# Mainboard.net
KiCad netlist of a schematic drawn in EAGLE
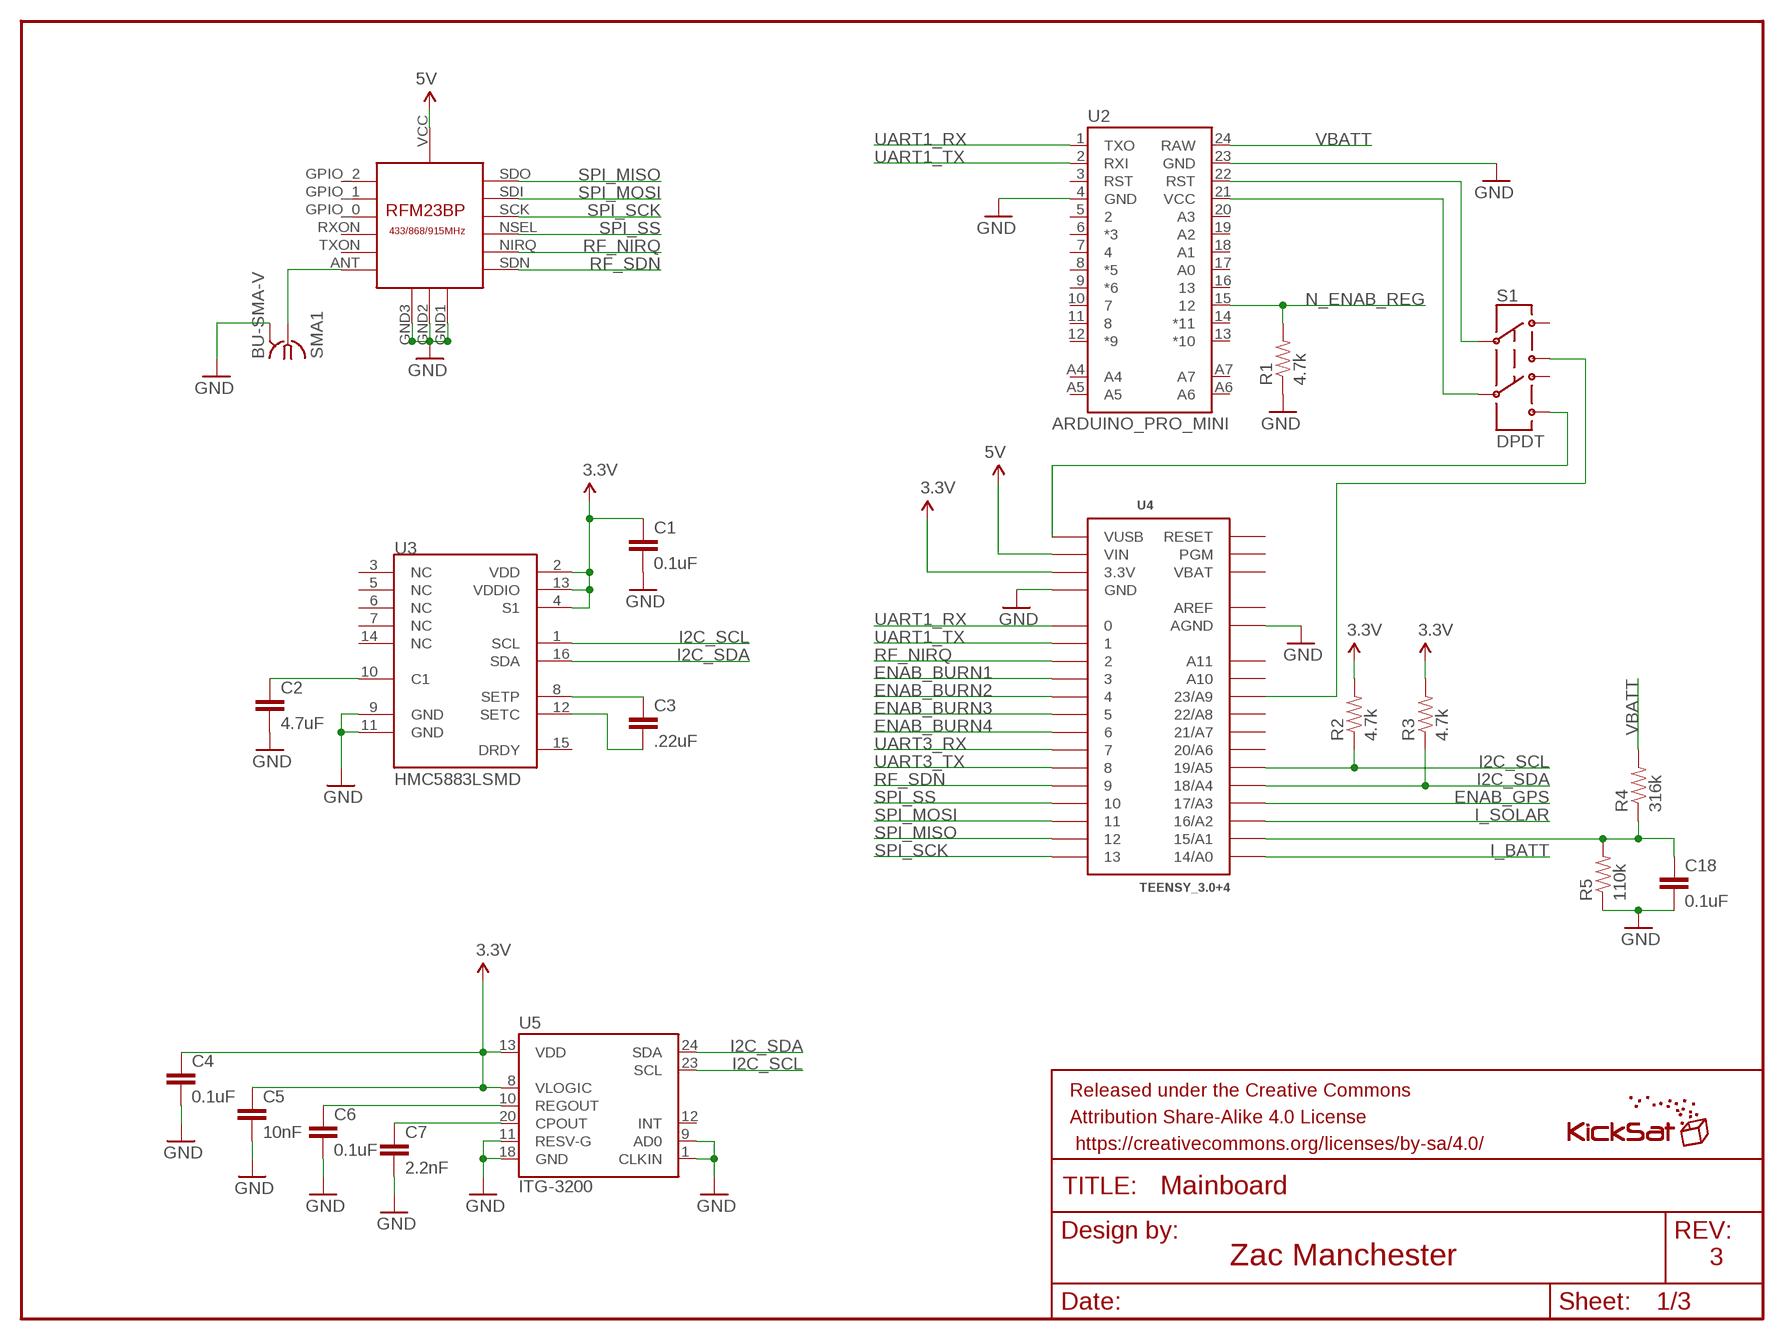
[diagram p0: schematic, sheet 1]
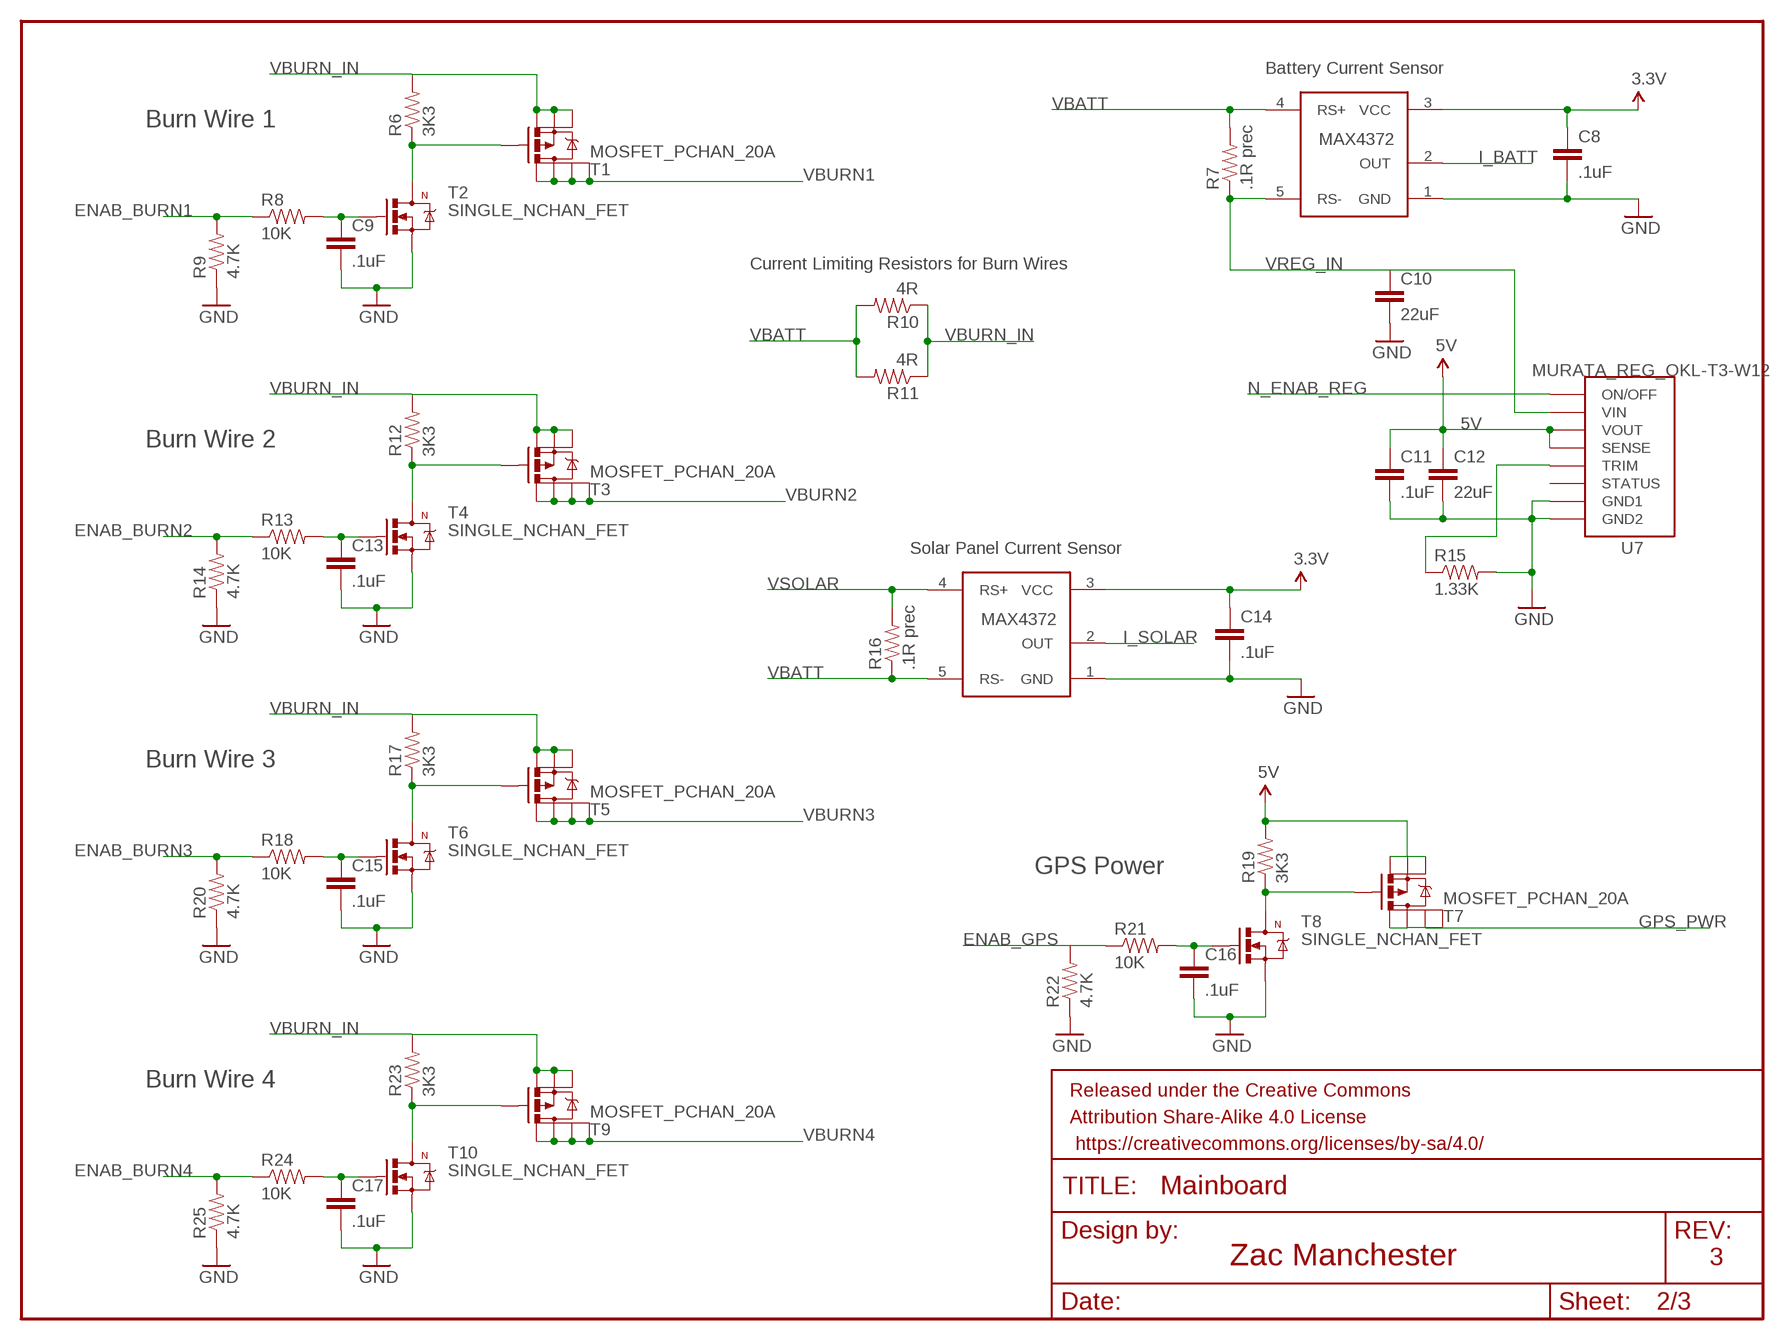
[diagram p1: schematic, sheet 2]
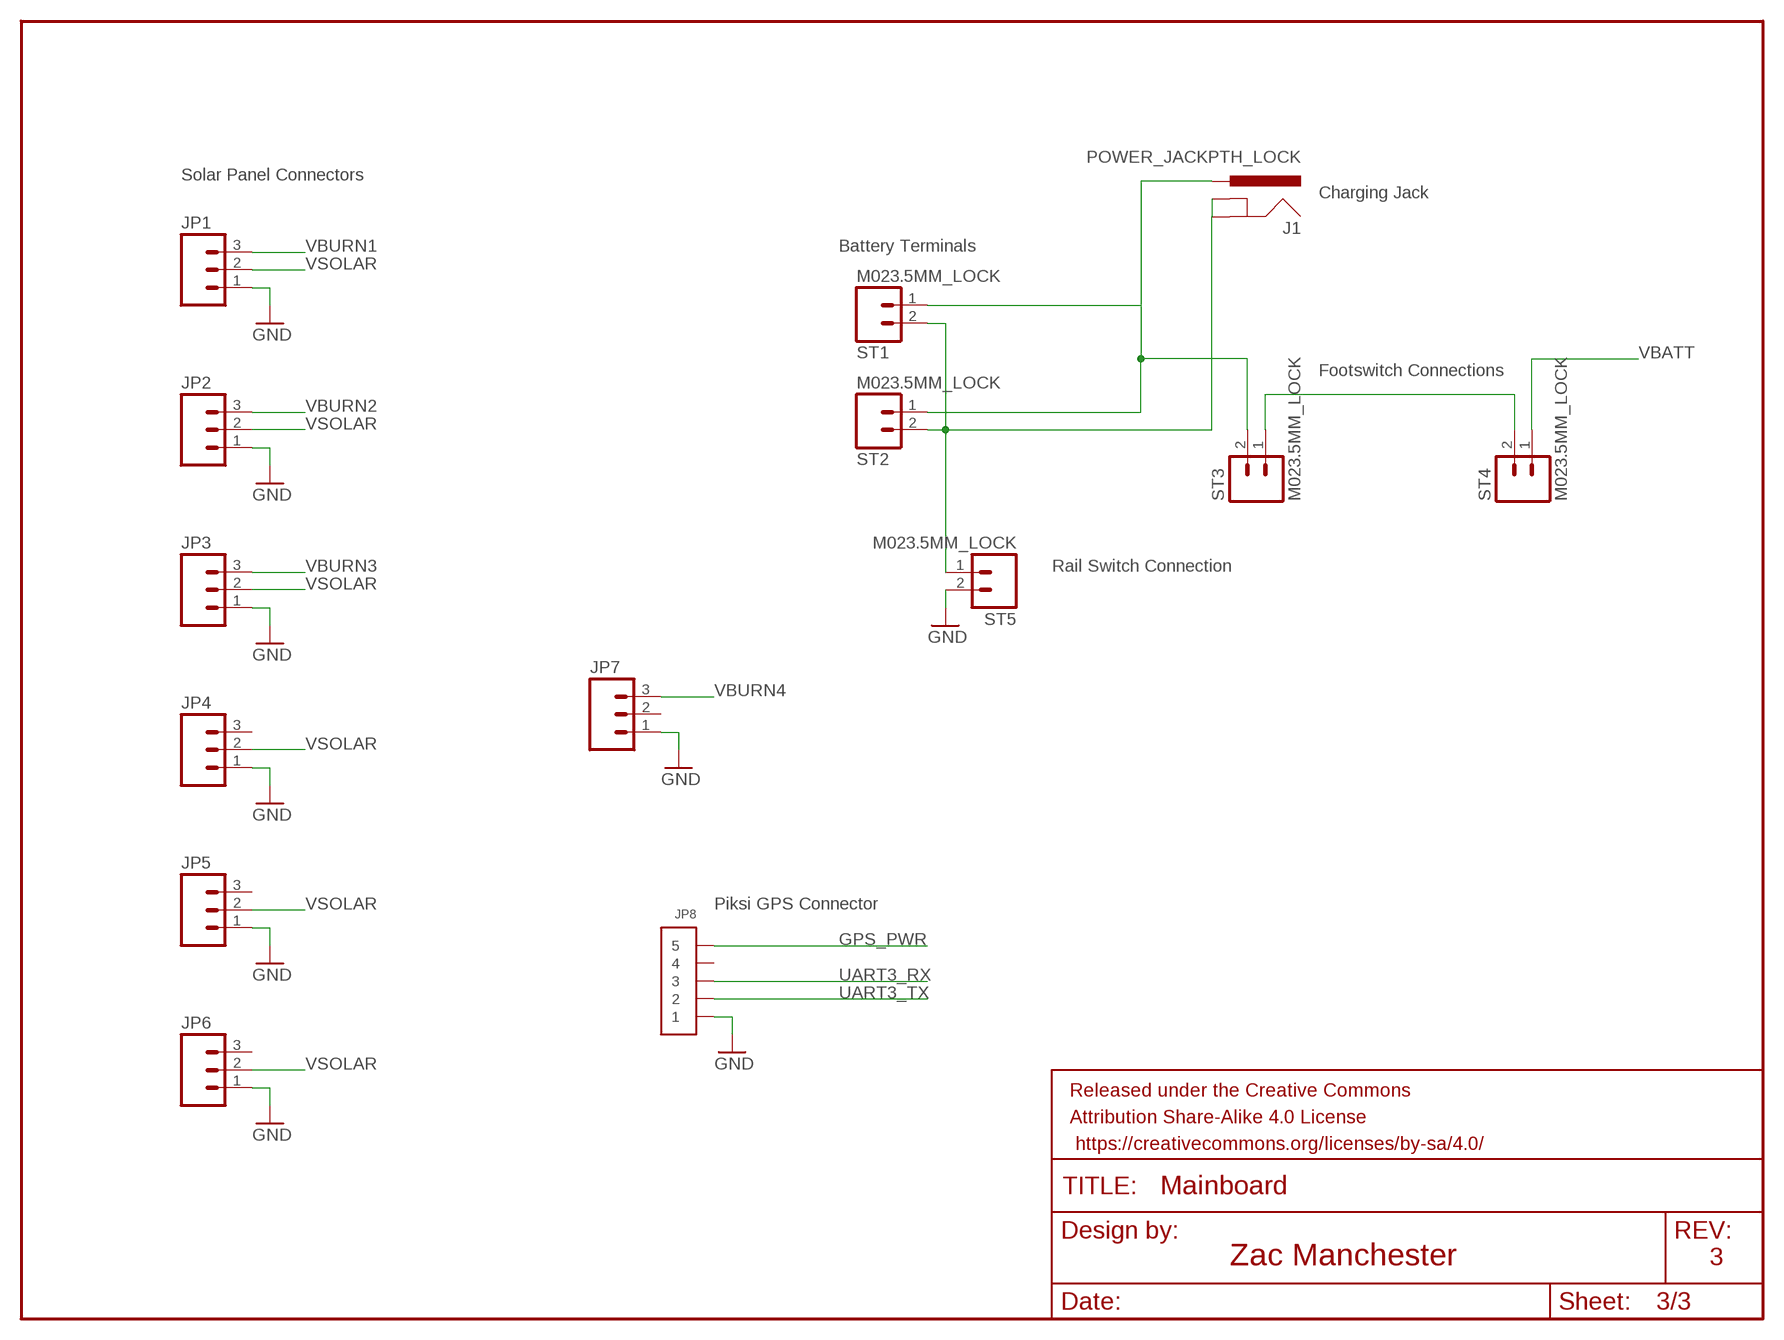
[diagram p2: schematic, sheet 3]

(export (version "E")
  (design (tool "Eeschema 10.0.6"))
  (components
    (comp (ref "C8")
      (value ".1uF")
      (footprint "eagle-import:0805")
      (libsource (lib "eagle-import") (part "CAP0805"))
    )
    (comp (ref "C9")
      (value ".1uF")
      (footprint "eagle-import:0805")
      (libsource (lib "eagle-import") (part "CAP0805"))
    )
    (comp (ref "C10")
      (value "22uF")
      (footprint "eagle-import:1206")
      (libsource (lib "eagle-import") (part "CAP1206"))
    )
    (comp (ref "C11")
      (value ".1uF")
      (footprint "eagle-import:0805")
      (libsource (lib "eagle-import") (part "CAP0805"))
    )
    (comp (ref "C12")
      (value "22uF")
      (footprint "eagle-import:1206")
      (libsource (lib "eagle-import") (part "CAP1206"))
    )
    (comp (ref "C13")
      (value ".1uF")
      (footprint "eagle-import:0805")
      (libsource (lib "eagle-import") (part "CAP0805"))
    )
    (comp (ref "C14")
      (value ".1uF")
      (footprint "eagle-import:0805")
      (libsource (lib "eagle-import") (part "CAP0805"))
    )
    (comp (ref "C15")
      (value ".1uF")
      (footprint "eagle-import:0805")
      (libsource (lib "eagle-import") (part "CAP0805"))
    )
    (comp (ref "C16")
      (value ".1uF")
      (footprint "eagle-import:0805")
      (libsource (lib "eagle-import") (part "CAP0805"))
    )
    (comp (ref "C17")
      (value ".1uF")
      (footprint "eagle-import:0805")
      (libsource (lib "eagle-import") (part "CAP0805"))
    )
    (comp (ref "FRAME2")
      (value "FRAME-LETTER")
      (footprint "eagle-import:CREATIVE_COMMONS")
      (libsource (lib "eagle-import") (part "FRAME-LETTER"))
    )
    (comp (ref "R6")
      (value "3K3")
      (footprint "eagle-import:0805")
      (libsource (lib "eagle-import") (part "RESISTOR0805-RES"))
    )
    (comp (ref "R7")
      (value ".1R prec")
      (footprint "eagle-import:0805")
      (libsource (lib "eagle-import") (part "RESISTOR0805-RES"))
    )
    (comp (ref "R8")
      (value "10K")
      (footprint "eagle-import:0805")
      (libsource (lib "eagle-import") (part "RESISTOR0805-RES"))
    )
    (comp (ref "R9")
      (value "4.7K")
      (footprint "eagle-import:0805")
      (libsource (lib "eagle-import") (part "RESISTOR0805-RES"))
    )
    (comp (ref "R10")
      (value "4R")
      (footprint "eagle-import:R2512")
      (libsource (lib "eagle-import") (part "RESISTOR2512"))
    )
    (comp (ref "R11")
      (value "4R")
      (footprint "eagle-import:R2512")
      (libsource (lib "eagle-import") (part "RESISTOR2512"))
    )
    (comp (ref "R12")
      (value "3K3")
      (footprint "eagle-import:0805")
      (libsource (lib "eagle-import") (part "RESISTOR0805-RES"))
    )
    (comp (ref "R13")
      (value "10K")
      (footprint "eagle-import:0805")
      (libsource (lib "eagle-import") (part "RESISTOR0805-RES"))
    )
    (comp (ref "R14")
      (value "4.7K")
      (footprint "eagle-import:0805")
      (libsource (lib "eagle-import") (part "RESISTOR0805-RES"))
    )
    (comp (ref "R15")
      (value "1.33K")
      (footprint "eagle-import:0805")
      (libsource (lib "eagle-import") (part "RESISTOR0805-RES"))
    )
    (comp (ref "R16")
      (value ".1R prec")
      (footprint "eagle-import:0805")
      (libsource (lib "eagle-import") (part "RESISTOR0805-RES"))
    )
    (comp (ref "R17")
      (value "3K3")
      (footprint "eagle-import:0805")
      (libsource (lib "eagle-import") (part "RESISTOR0805-RES"))
    )
    (comp (ref "R18")
      (value "10K")
      (footprint "eagle-import:0805")
      (libsource (lib "eagle-import") (part "RESISTOR0805-RES"))
    )
    (comp (ref "R19")
      (value "3K3")
      (footprint "eagle-import:0805")
      (libsource (lib "eagle-import") (part "RESISTOR0805-RES"))
    )
    (comp (ref "R20")
      (value "4.7K")
      (footprint "eagle-import:0805")
      (libsource (lib "eagle-import") (part "RESISTOR0805-RES"))
    )
    (comp (ref "R21")
      (value "10K")
      (footprint "eagle-import:0805")
      (libsource (lib "eagle-import") (part "RESISTOR0805-RES"))
    )
    (comp (ref "R22")
      (value "4.7K")
      (footprint "eagle-import:0805")
      (libsource (lib "eagle-import") (part "RESISTOR0805-RES"))
    )
    (comp (ref "R23")
      (value "3K3")
      (footprint "eagle-import:0805")
      (libsource (lib "eagle-import") (part "RESISTOR0805-RES"))
    )
    (comp (ref "R24")
      (value "10K")
      (footprint "eagle-import:0805")
      (libsource (lib "eagle-import") (part "RESISTOR0805-RES"))
    )
    (comp (ref "R25")
      (value "4.7K")
      (footprint "eagle-import:0805")
      (libsource (lib "eagle-import") (part "RESISTOR0805-RES"))
    )
    (comp (ref "T1")
      (value "MOSFET_PCHAN_20A")
      (footprint "eagle-import:SO8")
      (libsource (lib "eagle-import") (part "MOSFET_PCHAN_20A"))
    )
    (comp (ref "T2")
      (value "SINGLE_NCHAN_FET")
      (footprint "eagle-import:SOT23-3")
      (libsource (lib "eagle-import") (part "SINGLE_NCHAN_FET"))
    )
    (comp (ref "T3")
      (value "MOSFET_PCHAN_20A")
      (footprint "eagle-import:SO8")
      (libsource (lib "eagle-import") (part "MOSFET_PCHAN_20A"))
    )
    (comp (ref "T4")
      (value "SINGLE_NCHAN_FET")
      (footprint "eagle-import:SOT23-3")
      (libsource (lib "eagle-import") (part "SINGLE_NCHAN_FET"))
    )
    (comp (ref "T5")
      (value "MOSFET_PCHAN_20A")
      (footprint "eagle-import:SO8")
      (libsource (lib "eagle-import") (part "MOSFET_PCHAN_20A"))
    )
    (comp (ref "T6")
      (value "SINGLE_NCHAN_FET")
      (footprint "eagle-import:SOT23-3")
      (libsource (lib "eagle-import") (part "SINGLE_NCHAN_FET"))
    )
    (comp (ref "T7")
      (value "MOSFET_PCHAN_20A")
      (footprint "eagle-import:SO8")
      (libsource (lib "eagle-import") (part "MOSFET_PCHAN_20A"))
    )
    (comp (ref "T8")
      (value "SINGLE_NCHAN_FET")
      (footprint "eagle-import:SOT23-3")
      (libsource (lib "eagle-import") (part "SINGLE_NCHAN_FET"))
    )
    (comp (ref "T9")
      (value "MOSFET_PCHAN_20A")
      (footprint "eagle-import:SO8")
      (libsource (lib "eagle-import") (part "MOSFET_PCHAN_20A"))
    )
    (comp (ref "T10")
      (value "SINGLE_NCHAN_FET")
      (footprint "eagle-import:SOT23-3")
      (libsource (lib "eagle-import") (part "SINGLE_NCHAN_FET"))
    )
    (comp (ref "U6")
      (value "CURRENT_MAX4372")
      (footprint "eagle-import:SOT23-5")
      (libsource (lib "eagle-import") (part "CURRENT_MAX4372"))
    )
    (comp (ref "U7")
      (value "MURATA_REG_OKL-T3-W12")
      (footprint "eagle-import:MURATA_REG_OKL-T6-W12")
      (libsource (lib "eagle-import") (part "MURATA_REG_OKL-T6-W12"))
    )
    (comp (ref "U8")
      (value "CURRENT_MAX4372")
      (footprint "eagle-import:SOT23-5")
      (libsource (lib "eagle-import") (part "CURRENT_MAX4372"))
    )
    (comp (ref "FRAME3")
      (value "FRAME-LETTER")
      (footprint "eagle-import:CREATIVE_COMMONS")
      (libsource (lib "eagle-import") (part "FRAME-LETTER"))
    )
    (comp (ref "J1")
      (value "POWER_JACKPTH_LOCK")
      (footprint "eagle-import:POWER_JACK_PTH_LOCK")
      (libsource (lib "eagle-import") (part "POWER_JACKPTH_LOCK"))
    )
    (comp (ref "JP1")
      (value "M03POLAR_LOCK")
      (footprint "eagle-import:MOLEX-1X3_LOCK")
      (libsource (lib "eagle-import") (part "M03POLAR_LOCK"))
    )
    (comp (ref "JP2")
      (value "M03POLAR_LOCK")
      (footprint "eagle-import:MOLEX-1X3_LOCK")
      (libsource (lib "eagle-import") (part "M03POLAR_LOCK"))
    )
    (comp (ref "JP3")
      (value "M03POLAR_LOCK")
      (footprint "eagle-import:MOLEX-1X3_LOCK")
      (libsource (lib "eagle-import") (part "M03POLAR_LOCK"))
    )
    (comp (ref "JP4")
      (value "M03POLAR_LOCK")
      (footprint "eagle-import:MOLEX-1X3_LOCK")
      (libsource (lib "eagle-import") (part "M03POLAR_LOCK"))
    )
    (comp (ref "JP5")
      (value "M03POLAR_LOCK")
      (footprint "eagle-import:MOLEX-1X3_LOCK")
      (libsource (lib "eagle-import") (part "M03POLAR_LOCK"))
    )
    (comp (ref "JP6")
      (value "M03POLAR_LOCK")
      (footprint "eagle-import:MOLEX-1X3_LOCK")
      (libsource (lib "eagle-import") (part "M03POLAR_LOCK"))
    )
    (comp (ref "JP7")
      (value "M03POLAR_LOCK")
      (footprint "eagle-import:MOLEX-1X3_LOCK")
      (libsource (lib "eagle-import") (part "M03POLAR_LOCK"))
    )
    (comp (ref "JP8")
      (value "CONN_5-1-53261")
      (footprint "eagle-import:PB-53261-05")
      (libsource (lib "eagle-import") (part "CONN_5-1-53261"))
    )
    (comp (ref "ST1")
      (value "M023.5MM_LOCK")
      (footprint "eagle-import:SCREWTERMINAL-3.5MM-2_LOCK")
      (libsource (lib "eagle-import") (part "M023.5MM_LOCK"))
    )
    (comp (ref "ST2")
      (value "M023.5MM_LOCK")
      (footprint "eagle-import:SCREWTERMINAL-3.5MM-2_LOCK")
      (libsource (lib "eagle-import") (part "M023.5MM_LOCK"))
    )
    (comp (ref "ST3")
      (value "M023.5MM_LOCK")
      (footprint "eagle-import:SCREWTERMINAL-3.5MM-2_LOCK")
      (libsource (lib "eagle-import") (part "M023.5MM_LOCK"))
    )
    (comp (ref "ST4")
      (value "M023.5MM_LOCK")
      (footprint "eagle-import:SCREWTERMINAL-3.5MM-2_LOCK")
      (libsource (lib "eagle-import") (part "M023.5MM_LOCK"))
    )
    (comp (ref "ST5")
      (value "M023.5MM_LOCK")
      (footprint "eagle-import:SCREWTERMINAL-3.5MM-2_LOCK")
      (libsource (lib "eagle-import") (part "M023.5MM_LOCK"))
    )
    (comp (ref "C1")
      (value "0.1uF")
      (footprint "eagle-import:0805")
      (libsource (lib "eagle-import") (part "CAP0805"))
    )
    (comp (ref "C2")
      (value "4.7uF")
      (footprint "eagle-import:0805")
      (libsource (lib "eagle-import") (part "CAP0805"))
    )
    (comp (ref "C3")
      (value ".22uF")
      (footprint "eagle-import:0805")
      (libsource (lib "eagle-import") (part "CAP0805"))
    )
    (comp (ref "C4")
      (value "0.1uF")
      (footprint "eagle-import:0805")
      (libsource (lib "eagle-import") (part "CAP0805"))
    )
    (comp (ref "C5")
      (value "10nF")
      (footprint "eagle-import:0805")
      (libsource (lib "eagle-import") (part "CAP0805"))
    )
    (comp (ref "C6")
      (value "0.1uF")
      (footprint "eagle-import:0805")
      (libsource (lib "eagle-import") (part "CAP0805"))
    )
    (comp (ref "C7")
      (value "2.2nF")
      (footprint "eagle-import:0805")
      (libsource (lib "eagle-import") (part "CAP0805"))
    )
    (comp (ref "C18")
      (value "0.1uF")
      (footprint "eagle-import:0805")
      (libsource (lib "eagle-import") (part "CAP0805"))
    )
    (comp (ref "FRAME1")
      (value "FRAME-LETTER")
      (footprint "eagle-import:CREATIVE_COMMONS")
      (libsource (lib "eagle-import") (part "FRAME-LETTER"))
    )
    (comp (ref "R1")
      (value "4.7k")
      (footprint "eagle-import:0805")
      (libsource (lib "eagle-import") (part "RESISTOR0805-RES"))
    )
    (comp (ref "R2")
      (value "4.7k")
      (footprint "eagle-import:0805")
      (libsource (lib "eagle-import") (part "RESISTOR0805-RES"))
    )
    (comp (ref "R3")
      (value "4.7k")
      (footprint "eagle-import:0805")
      (libsource (lib "eagle-import") (part "RESISTOR0805-RES"))
    )
    (comp (ref "R4")
      (value "316k")
      (footprint "eagle-import:0805")
      (libsource (lib "eagle-import") (part "RESISTOR0805-RES"))
    )
    (comp (ref "R5")
      (value "110k")
      (footprint "eagle-import:0805")
      (libsource (lib "eagle-import") (part "RESISTOR0805-RES"))
    )
    (comp (ref "S1")
      (value "DPDT")
      (footprint "eagle-import:AYZ0202")
      (libsource (lib "eagle-import") (part "SWITCH-DPDTAYZ0202"))
    )
    (comp (ref "SMA1")
      (value "BU-SMA-V")
      (footprint "eagle-import:BU-SMA-V")
      (libsource (lib "eagle-import") (part "BU-SMA-V"))
    )
    (comp (ref "U$3")
      (value "KICKSAT_LOGO")
      (footprint "eagle-import:KICKSAT_LOGO")
      (libsource (lib "eagle-import") (part "KICKSAT_LOGO"))
    )
    (comp (ref "U1")
      (value "RFM23BP")
      (footprint "eagle-import:RFM23BP")
      (libsource (lib "eagle-import") (part "RFM23BP"))
    )
    (comp (ref "U2")
      (value "ARDUINO_PRO_MINI")
      (footprint "eagle-import:ARDUINO_PRO_MINI")
      (libsource (lib "eagle-import") (part "ARDUINO_PRO_MINI"))
    )
    (comp (ref "U3")
      (value "HMC5883LSMD")
      (footprint "eagle-import:16LPCC")
      (libsource (lib "eagle-import") (part "HMC5883LSMD"))
    )
    (comp (ref "U4")
      (value "TEENSY_3.0+4")
      (footprint "eagle-import:TEENSY_3.0+4")
      (libsource (lib "eagle-import") (part "TEENSY_3.0+4"))
    )
    (comp (ref "U5")
      (value "ITG-3200")
      (footprint "eagle-import:QFN-24")
      (libsource (lib "eagle-import") (part "ITG-3200"))
    )
  )
  (nets
    (net (code "1") (name "3.3V") (class "Default")
      (node (ref "C1") (pin "1") (pinfunction "1_1") (pintype "passive"))
      (node (ref "C14") (pin "1") (pinfunction "1_1") (pintype "passive"))
      (node (ref "C4") (pin "1") (pinfunction "1_1") (pintype "passive"))
      (node (ref "C5") (pin "1") (pinfunction "1_1") (pintype "passive"))
      (node (ref "C8") (pin "1") (pinfunction "1_1") (pintype "passive"))
      (node (ref "R2") (pin "2") (pinfunction "2_2") (pintype "passive"))
      (node (ref "R3") (pin "2") (pinfunction "2_2") (pintype "passive"))
      (node (ref "U3") (pin "13") (pinfunction "VDDIO_13") (pintype "bidirectional"))
      (node (ref "U3") (pin "2") (pinfunction "VDD_2") (pintype "bidirectional"))
      (node (ref "U3") (pin "4") (pinfunction "S1_4") (pintype "bidirectional"))
      (node (ref "U4") (pin "3.3V") (pinfunction "3.3V_3.3V") (pintype "power_in"))
      (node (ref "U4") (pin "3.3V1") (pinfunction "3.3V_3.3V1") (pintype "power_in"))
      (node (ref "U5") (pin "13") (pinfunction "VDD_13") (pintype "bidirectional"))
      (node (ref "U5") (pin "8") (pinfunction "VLOGIC_8") (pintype "bidirectional"))
      (node (ref "U6") (pin "3") (pinfunction "VCC_3") (pintype "bidirectional"))
      (node (ref "U8") (pin "3") (pinfunction "VCC_3") (pintype "bidirectional"))
    )
    (net (code "2") (name "5V") (class "Default")
      (node (ref "C11") (pin "1") (pinfunction "1_1") (pintype "passive"))
      (node (ref "C12") (pin "1") (pinfunction "1_1") (pintype "passive"))
      (node (ref "R19") (pin "2") (pinfunction "2_2") (pintype "passive"))
      (node (ref "T7") (pin "1") (pinfunction "S_1") (pintype "passive"))
      (node (ref "T7") (pin "2") (pinfunction "S_2") (pintype "passive"))
      (node (ref "T7") (pin "3") (pinfunction "S_3") (pintype "passive"))
      (node (ref "U1") (pin "VCC") (pinfunction "VCC_VCC") (pintype "power_in"))
      (node (ref "U4") (pin "VIN") (pinfunction "VIN_VIN") (pintype "power_in"))
      (node (ref "U7") (pin "4") (pinfunction "VOUT_4") (pintype "bidirectional"))
      (node (ref "U7") (pin "5") (pinfunction "SENSE_5") (pintype "bidirectional"))
    )
    (net (code "3") (name "AREF") (class "Default")
      (node (ref "U4") (pin "AREF") (pinfunction "AREF_AREF") (pintype "power_in"))
    )
    (net (code "4") (name "ENAB_BURN1") (class "Default")
      (node (ref "R8") (pin "1") (pinfunction "1_1") (pintype "passive"))
      (node (ref "R9") (pin "2") (pinfunction "2_2") (pintype "passive"))
      (node (ref "U4") (pin "3") (pinfunction "3_3") (pintype "bidirectional"))
    )
    (net (code "5") (name "ENAB_BURN2") (class "Default")
      (node (ref "R13") (pin "1") (pinfunction "1_1") (pintype "passive"))
      (node (ref "R14") (pin "2") (pinfunction "2_2") (pintype "passive"))
      (node (ref "U4") (pin "4") (pinfunction "4_4") (pintype "bidirectional"))
    )
    (net (code "6") (name "ENAB_BURN3") (class "Default")
      (node (ref "R18") (pin "1") (pinfunction "1_1") (pintype "passive"))
      (node (ref "R20") (pin "2") (pinfunction "2_2") (pintype "passive"))
      (node (ref "U4") (pin "5") (pinfunction "5_5") (pintype "bidirectional"))
    )
    (net (code "7") (name "ENAB_BURN4") (class "Default")
      (node (ref "R24") (pin "1") (pinfunction "1_1") (pintype "passive"))
      (node (ref "R25") (pin "2") (pinfunction "2_2") (pintype "passive"))
      (node (ref "U4") (pin "6") (pinfunction "6_6") (pintype "bidirectional"))
    )
    (net (code "8") (name "ENAB_GPS") (class "Default")
      (node (ref "R21") (pin "1") (pinfunction "1_1") (pintype "passive"))
      (node (ref "R22") (pin "2") (pinfunction "2_2") (pintype "passive"))
      (node (ref "U4") (pin "17/A3") (pinfunction "17/A3_17/A3") (pintype "bidirectional"))
    )
    (net (code "9") (name "GND") (class "Default")
      (node (ref "C1") (pin "2") (pinfunction "2_2") (pintype "passive"))
      (node (ref "C10") (pin "2") (pinfunction "2_2") (pintype "passive"))
      (node (ref "C11") (pin "2") (pinfunction "2_2") (pintype "passive"))
      (node (ref "C12") (pin "2") (pinfunction "2_2") (pintype "passive"))
      (node (ref "C13") (pin "2") (pinfunction "2_2") (pintype "passive"))
      (node (ref "C14") (pin "2") (pinfunction "2_2") (pintype "passive"))
      (node (ref "C15") (pin "2") (pinfunction "2_2") (pintype "passive"))
      (node (ref "C16") (pin "2") (pinfunction "2_2") (pintype "passive"))
      (node (ref "C17") (pin "2") (pinfunction "2_2") (pintype "passive"))
      (node (ref "C18") (pin "2") (pinfunction "2_2") (pintype "passive"))
      (node (ref "C2") (pin "2") (pinfunction "2_2") (pintype "passive"))
      (node (ref "C4") (pin "2") (pinfunction "2_2") (pintype "passive"))
      (node (ref "C5") (pin "2") (pinfunction "2_2") (pintype "passive"))
      (node (ref "C6") (pin "2") (pinfunction "2_2") (pintype "passive"))
      (node (ref "C7") (pin "2") (pinfunction "2_2") (pintype "passive"))
      (node (ref "C8") (pin "2") (pinfunction "2_2") (pintype "passive"))
      (node (ref "C9") (pin "2") (pinfunction "2_2") (pintype "passive"))
      (node (ref "JP1") (pin "1") (pinfunction "1_1") (pintype "passive"))
      (node (ref "JP2") (pin "1") (pinfunction "1_1") (pintype "passive"))
      (node (ref "JP3") (pin "1") (pinfunction "1_1") (pintype "passive"))
      (node (ref "JP4") (pin "1") (pinfunction "1_1") (pintype "passive"))
      (node (ref "JP5") (pin "1") (pinfunction "1_1") (pintype "passive"))
      (node (ref "JP6") (pin "1") (pinfunction "1_1") (pintype "passive"))
      (node (ref "JP7") (pin "1") (pinfunction "1_1") (pintype "passive"))
      (node (ref "JP8") (pin "1") (pinfunction "1_1") (pintype "bidirectional"))
      (node (ref "R1") (pin "1") (pinfunction "1_1") (pintype "passive"))
      (node (ref "R14") (pin "1") (pinfunction "1_1") (pintype "passive"))
      (node (ref "R15") (pin "2") (pinfunction "2_2") (pintype "passive"))
      (node (ref "R20") (pin "1") (pinfunction "1_1") (pintype "passive"))
      (node (ref "R22") (pin "1") (pinfunction "1_1") (pintype "passive"))
      (node (ref "R25") (pin "1") (pinfunction "1_1") (pintype "passive"))
      (node (ref "R5") (pin "1") (pinfunction "1_1") (pintype "passive"))
      (node (ref "R9") (pin "1") (pinfunction "1_1") (pintype "passive"))
      (node (ref "SMA1") (pin "2") (pinfunction "2_2") (pintype "passive"))
      (node (ref "SMA1") (pin "3") (pinfunction "2_3") (pintype "passive"))
      (node (ref "SMA1") (pin "4") (pinfunction "2_4") (pintype "passive"))
      (node (ref "SMA1") (pin "5") (pinfunction "2_5") (pintype "passive"))
      (node (ref "ST5") (pin "2") (pinfunction "2_2") (pintype "passive"))
      (node (ref "T10") (pin "2") (pinfunction "S_2") (pintype "passive"))
      (node (ref "T2") (pin "2") (pinfunction "S_2") (pintype "passive"))
      (node (ref "T4") (pin "2") (pinfunction "S_2") (pintype "passive"))
      (node (ref "T6") (pin "2") (pinfunction "S_2") (pintype "passive"))
      (node (ref "T8") (pin "2") (pinfunction "S_2") (pintype "passive"))
      (node (ref "U1") (pin "GND1") (pinfunction "GND1_GND1") (pintype "power_in"))
      (node (ref "U1") (pin "GND2") (pinfunction "GND2_GND2") (pintype "power_in"))
      (node (ref "U1") (pin "GND3") (pinfunction "GND3_GND3") (pintype "power_in"))
      (node (ref "U2") (pin "23") (pinfunction "GND_23") (pintype "bidirectional"))
      (node (ref "U2") (pin "4") (pinfunction "GND_4") (pintype "bidirectional"))
      (node (ref "U3") (pin "11") (pinfunction "GND_11") (pintype "bidirectional"))
      (node (ref "U3") (pin "9") (pinfunction "GND_9") (pintype "bidirectional"))
      (node (ref "U4") (pin "AGND") (pinfunction "AGND_AGND") (pintype "power_in"))
      (node (ref "U4") (pin "GND") (pinfunction "GND_GND") (pintype "power_in"))
      (node (ref "U4") (pin "GND1") (pinfunction "GND_GND1") (pintype "power_in"))
      (node (ref "U5") (pin "1") (pinfunction "CLKIN_1") (pintype "bidirectional"))
      (node (ref "U5") (pin "11") (pinfunction "RESV-G_11") (pintype "bidirectional"))
      (node (ref "U5") (pin "18") (pinfunction "GND_18") (pintype "bidirectional"))
      (node (ref "U5") (pin "9") (pinfunction "AD0_9") (pintype "bidirectional"))
      (node (ref "U6") (pin "1") (pinfunction "GND_1") (pintype "bidirectional"))
      (node (ref "U7") (pin "3") (pinfunction "GND1_3") (pintype "bidirectional"))
      (node (ref "U7") (pin "7") (pinfunction "GND2_7") (pintype "bidirectional"))
      (node (ref "U8") (pin "1") (pinfunction "GND_1") (pintype "bidirectional"))
    )
    (net (code "10") (name "GPS_PWR") (class "Default")
      (node (ref "JP8") (pin "5") (pinfunction "5_5") (pintype "bidirectional"))
      (node (ref "T7") (pin "5") (pinfunction "D_5") (pintype "passive"))
      (node (ref "T7") (pin "6") (pinfunction "D_6") (pintype "passive"))
      (node (ref "T7") (pin "7") (pinfunction "D_7") (pintype "passive"))
      (node (ref "T7") (pin "8") (pinfunction "D_8") (pintype "passive"))
    )
    (net (code "11") (name "I2C_SCL") (class "Default")
      (node (ref "R2") (pin "1") (pinfunction "1_1") (pintype "passive"))
      (node (ref "U3") (pin "1") (pinfunction "SCL_1") (pintype "bidirectional"))
      (node (ref "U4") (pin "19/A5") (pinfunction "19/A5_19/A5") (pintype "bidirectional"))
      (node (ref "U5") (pin "23") (pinfunction "SCL_23") (pintype "bidirectional"))
    )
    (net (code "12") (name "I2C_SDA") (class "Default")
      (node (ref "R3") (pin "1") (pinfunction "1_1") (pintype "passive"))
      (node (ref "U3") (pin "16") (pinfunction "SDA_16") (pintype "bidirectional"))
      (node (ref "U4") (pin "18/A4") (pinfunction "18/A4_18/A4") (pintype "bidirectional"))
      (node (ref "U5") (pin "24") (pinfunction "SDA_24") (pintype "bidirectional"))
    )
    (net (code "13") (name "I_BATT") (class "Default")
      (node (ref "U4") (pin "14/A0") (pinfunction "14/A0_14/A0") (pintype "bidirectional"))
      (node (ref "U6") (pin "2") (pinfunction "OUT_2") (pintype "bidirectional"))
    )
    (net (code "14") (name "I_SOLAR") (class "Default")
      (node (ref "U4") (pin "16/A2") (pinfunction "16/A2_16/A2") (pintype "bidirectional"))
      (node (ref "U8") (pin "2") (pinfunction "OUT_2") (pintype "bidirectional"))
    )
    (net (code "15") (name "N_ENAB_REG") (class "Default")
      (node (ref "R1") (pin "2") (pinfunction "2_2") (pintype "passive"))
      (node (ref "U2") (pin "15") (pinfunction "12_15") (pintype "bidirectional"))
      (node (ref "U7") (pin "1") (pinfunction "ON/OFF_1") (pintype "bidirectional"))
    )
    (net (code "16") (name "Net-(C18-Pad1)") (class "Default")
      (node (ref "C18") (pin "1") (pinfunction "1_1") (pintype "passive"))
      (node (ref "R4") (pin "1") (pinfunction "1_1") (pintype "passive"))
      (node (ref "R5") (pin "2") (pinfunction "2_2") (pintype "passive"))
      (node (ref "U4") (pin "15/A1") (pinfunction "15/A1_15/A1") (pintype "bidirectional"))
    )
    (net (code "17") (name "Net-(J1-PadGND)") (class "Default")
      (node (ref "J1") (pin "GND") (pinfunction "GND_GND") (pintype "bidirectional"))
      (node (ref "J1") (pin "GNDBREAK") (pinfunction "GNDBREAK_GNDBREAK") (pintype "bidirectional"))
      (node (ref "ST1") (pin "2") (pinfunction "2_2") (pintype "passive"))
      (node (ref "ST2") (pin "2") (pinfunction "2_2") (pintype "passive"))
      (node (ref "ST5") (pin "1") (pinfunction "1_1") (pintype "passive"))
    )
    (net (code "18") (name "Net-(J1-PadPWR)") (class "Default")
      (node (ref "J1") (pin "PWR") (pinfunction "PWR_PWR") (pintype "bidirectional"))
      (node (ref "ST1") (pin "1") (pinfunction "1_1") (pintype "passive"))
      (node (ref "ST2") (pin "1") (pinfunction "1_1") (pintype "passive"))
      (node (ref "ST3") (pin "2") (pinfunction "2_2") (pintype "passive"))
    )
    (net (code "19") (name "Net-(S1-Pad2)") (class "Default")
      (node (ref "S1") (pin "2") (pinfunction "2_2") (pintype "bidirectional"))
      (node (ref "U2") (pin "22") (pinfunction "RST_22") (pintype "bidirectional"))
    )
    (net (code "20") (name "Net-(S1-Pad3)") (class "Default")
      (node (ref "S1") (pin "3") (pinfunction "3_3") (pintype "bidirectional"))
      (node (ref "U4") (pin "23/A9") (pinfunction "23/A9_23/A9") (pintype "bidirectional"))
    )
    (net (code "21") (name "Net-(S1-Pad6)") (class "Default")
      (node (ref "S1") (pin "6") (pinfunction "6_6") (pintype "bidirectional"))
      (node (ref "U4") (pin "VUSB") (pinfunction "VUSB_VUSB") (pintype "power_in"))
    )
    (net (code "22") (name "Net-(SMA1-Pad1)") (class "Default")
      (node (ref "SMA1") (pin "1") (pinfunction "1_1") (pintype "passive"))
      (node (ref "U1") (pin "ANT") (pinfunction "ANT_ANT") (pintype "bidirectional"))
    )
    (net (code "23") (name "Net-(ST3-Pad1)") (class "Default")
      (node (ref "ST3") (pin "1") (pinfunction "1_1") (pintype "passive"))
      (node (ref "ST4") (pin "2") (pinfunction "2_2") (pintype "passive"))
    )
    (net (code "24") (name "Net-(T1-G)") (class "Default")
      (node (ref "R6") (pin "1") (pinfunction "1_1") (pintype "passive"))
      (node (ref "T1") (pin "4") (pinfunction "G_4") (pintype "passive"))
      (node (ref "T2") (pin "3") (pinfunction "D_3") (pintype "passive"))
    )
    (net (code "25") (name "Net-(T2-G)") (class "Default")
      (node (ref "C9") (pin "1") (pinfunction "1_1") (pintype "passive"))
      (node (ref "R8") (pin "2") (pinfunction "2_2") (pintype "passive"))
      (node (ref "T2") (pin "1") (pinfunction "G_1") (pintype "passive"))
    )
    (net (code "26") (name "Net-(T3-G)") (class "Default")
      (node (ref "R12") (pin "1") (pinfunction "1_1") (pintype "passive"))
      (node (ref "T3") (pin "4") (pinfunction "G_4") (pintype "passive"))
      (node (ref "T4") (pin "3") (pinfunction "D_3") (pintype "passive"))
    )
    (net (code "27") (name "Net-(T4-G)") (class "Default")
      (node (ref "C13") (pin "1") (pinfunction "1_1") (pintype "passive"))
      (node (ref "R13") (pin "2") (pinfunction "2_2") (pintype "passive"))
      (node (ref "T4") (pin "1") (pinfunction "G_1") (pintype "passive"))
    )
    (net (code "28") (name "Net-(T5-G)") (class "Default")
      (node (ref "R17") (pin "1") (pinfunction "1_1") (pintype "passive"))
      (node (ref "T5") (pin "4") (pinfunction "G_4") (pintype "passive"))
      (node (ref "T6") (pin "3") (pinfunction "D_3") (pintype "passive"))
    )
    (net (code "29") (name "Net-(T6-G)") (class "Default")
      (node (ref "C15") (pin "1") (pinfunction "1_1") (pintype "passive"))
      (node (ref "R18") (pin "2") (pinfunction "2_2") (pintype "passive"))
      (node (ref "T6") (pin "1") (pinfunction "G_1") (pintype "passive"))
    )
    (net (code "30") (name "Net-(T7-G)") (class "Default")
      (node (ref "R19") (pin "1") (pinfunction "1_1") (pintype "passive"))
      (node (ref "T7") (pin "4") (pinfunction "G_4") (pintype "passive"))
      (node (ref "T8") (pin "3") (pinfunction "D_3") (pintype "passive"))
    )
    (net (code "31") (name "Net-(T8-G)") (class "Default")
      (node (ref "C16") (pin "1") (pinfunction "1_1") (pintype "passive"))
      (node (ref "R21") (pin "2") (pinfunction "2_2") (pintype "passive"))
      (node (ref "T8") (pin "1") (pinfunction "G_1") (pintype "passive"))
    )
    (net (code "32") (name "Net-(T10-D)") (class "Default")
      (node (ref "R23") (pin "1") (pinfunction "1_1") (pintype "passive"))
      (node (ref "T10") (pin "3") (pinfunction "D_3") (pintype "passive"))
      (node (ref "T9") (pin "4") (pinfunction "G_4") (pintype "passive"))
    )
    (net (code "33") (name "Net-(T10-G)") (class "Default")
      (node (ref "C17") (pin "1") (pinfunction "1_1") (pintype "passive"))
      (node (ref "R24") (pin "2") (pinfunction "2_2") (pintype "passive"))
      (node (ref "T10") (pin "1") (pinfunction "G_1") (pintype "passive"))
    )
    (net (code "34") (name "Net-(U2-VCC)") (class "Default")
      (node (ref "S1") (pin "5") (pinfunction "5_5") (pintype "bidirectional"))
      (node (ref "U2") (pin "21") (pinfunction "VCC_21") (pintype "bidirectional"))
    )
    (net (code "35") (name "Net-(U3-C1)") (class "Default")
      (node (ref "C2") (pin "1") (pinfunction "1_1") (pintype "passive"))
      (node (ref "U3") (pin "10") (pinfunction "C1_10") (pintype "bidirectional"))
    )
    (net (code "36") (name "Net-(U3-SETC)") (class "Default")
      (node (ref "C3") (pin "2") (pinfunction "2_2") (pintype "passive"))
      (node (ref "U3") (pin "12") (pinfunction "SETC_12") (pintype "bidirectional"))
    )
    (net (code "37") (name "Net-(U3-SETP)") (class "Default")
      (node (ref "C3") (pin "1") (pinfunction "1_1") (pintype "passive"))
      (node (ref "U3") (pin "8") (pinfunction "SETP_8") (pintype "bidirectional"))
    )
    (net (code "38") (name "Net-(U5-CPOUT)") (class "Default")
      (node (ref "C7") (pin "1") (pinfunction "1_1") (pintype "passive"))
      (node (ref "U5") (pin "20") (pinfunction "CPOUT_20") (pintype "bidirectional"))
    )
    (net (code "39") (name "Net-(U5-REGOUT)") (class "Default")
      (node (ref "C6") (pin "1") (pinfunction "1_1") (pintype "passive"))
      (node (ref "U5") (pin "10") (pinfunction "REGOUT_10") (pintype "bidirectional"))
    )
    (net (code "40") (name "Net-(U7-TRIM)") (class "Default")
      (node (ref "R15") (pin "1") (pinfunction "1_1") (pintype "passive"))
      (node (ref "U7") (pin "6") (pinfunction "TRIM_6") (pintype "bidirectional"))
    )
    (net (code "41") (name "RF_NIRQ") (class "Default")
      (node (ref "U1") (pin "NIRQ") (pinfunction "NIRQ_NIRQ") (pintype "bidirectional"))
      (node (ref "U4") (pin "2") (pinfunction "2_2") (pintype "bidirectional"))
    )
    (net (code "42") (name "RF_SDN") (class "Default")
      (node (ref "U1") (pin "SDN") (pinfunction "SDN_SDN") (pintype "bidirectional"))
      (node (ref "U4") (pin "9") (pinfunction "9_9") (pintype "bidirectional"))
    )
    (net (code "43") (name "SPI_MISO") (class "Default")
      (node (ref "U1") (pin "SDO") (pinfunction "SDO_SDO") (pintype "bidirectional"))
      (node (ref "U4") (pin "12") (pinfunction "12_12") (pintype "bidirectional"))
    )
    (net (code "44") (name "SPI_MOSI") (class "Default")
      (node (ref "U1") (pin "SDI") (pinfunction "SDI_SDI") (pintype "bidirectional"))
      (node (ref "U4") (pin "11") (pinfunction "11_11") (pintype "bidirectional"))
    )
    (net (code "45") (name "SPI_SCK") (class "Default")
      (node (ref "U1") (pin "SCK") (pinfunction "SCK_SCK") (pintype "bidirectional"))
      (node (ref "U4") (pin "13") (pinfunction "13_13") (pintype "bidirectional"))
    )
    (net (code "46") (name "SPI_SS") (class "Default")
      (node (ref "U1") (pin "NSEL") (pinfunction "NSEL_NSEL") (pintype "bidirectional"))
      (node (ref "U4") (pin "10") (pinfunction "10_10") (pintype "bidirectional"))
    )
    (net (code "47") (name "UART1_RX") (class "Default")
      (node (ref "U2") (pin "1") (pinfunction "TXO_1") (pintype "bidirectional"))
      (node (ref "U4") (pin "0") (pinfunction "0_0") (pintype "bidirectional"))
    )
    (net (code "48") (name "UART1_TX") (class "Default")
      (node (ref "U2") (pin "2") (pinfunction "RXI_2") (pintype "bidirectional"))
      (node (ref "U4") (pin "1") (pinfunction "1_1") (pintype "bidirectional"))
    )
    (net (code "49") (name "UART3_RX") (class "Default")
      (node (ref "JP8") (pin "3") (pinfunction "3_3") (pintype "bidirectional"))
      (node (ref "U4") (pin "7") (pinfunction "7_7") (pintype "bidirectional"))
    )
    (net (code "50") (name "UART3_TX") (class "Default")
      (node (ref "JP8") (pin "2") (pinfunction "2_2") (pintype "bidirectional"))
      (node (ref "U4") (pin "8") (pinfunction "8_8") (pintype "bidirectional"))
    )
    (net (code "51") (name "VBAT") (class "Default")
      (node (ref "U4") (pin "VBAT") (pinfunction "VBAT_VBAT") (pintype "power_in"))
    )
    (net (code "52") (name "VBATT") (class "Default")
      (node (ref "R10") (pin "2") (pinfunction "2_2") (pintype "passive"))
      (node (ref "R11") (pin "2") (pinfunction "2_2") (pintype "passive"))
      (node (ref "R16") (pin "1") (pinfunction "1_1") (pintype "passive"))
      (node (ref "R4") (pin "2") (pinfunction "2_2") (pintype "passive"))
      (node (ref "R7") (pin "2") (pinfunction "2_2") (pintype "passive"))
      (node (ref "ST4") (pin "1") (pinfunction "1_1") (pintype "passive"))
      (node (ref "U2") (pin "24") (pinfunction "RAW_24") (pintype "bidirectional"))
      (node (ref "U6") (pin "4") (pinfunction "RS+_4") (pintype "bidirectional"))
      (node (ref "U8") (pin "5") (pinfunction "RS-_5") (pintype "bidirectional"))
    )
    (net (code "53") (name "VBURN1") (class "Default")
      (node (ref "JP1") (pin "3") (pinfunction "3_3") (pintype "passive"))
      (node (ref "T1") (pin "5") (pinfunction "D_5") (pintype "passive"))
      (node (ref "T1") (pin "6") (pinfunction "D_6") (pintype "passive"))
      (node (ref "T1") (pin "7") (pinfunction "D_7") (pintype "passive"))
      (node (ref "T1") (pin "8") (pinfunction "D_8") (pintype "passive"))
    )
    (net (code "54") (name "VBURN2") (class "Default")
      (node (ref "JP2") (pin "3") (pinfunction "3_3") (pintype "passive"))
      (node (ref "T3") (pin "5") (pinfunction "D_5") (pintype "passive"))
      (node (ref "T3") (pin "6") (pinfunction "D_6") (pintype "passive"))
      (node (ref "T3") (pin "7") (pinfunction "D_7") (pintype "passive"))
      (node (ref "T3") (pin "8") (pinfunction "D_8") (pintype "passive"))
    )
    (net (code "55") (name "VBURN3") (class "Default")
      (node (ref "JP3") (pin "3") (pinfunction "3_3") (pintype "passive"))
      (node (ref "T5") (pin "5") (pinfunction "D_5") (pintype "passive"))
      (node (ref "T5") (pin "6") (pinfunction "D_6") (pintype "passive"))
      (node (ref "T5") (pin "7") (pinfunction "D_7") (pintype "passive"))
      (node (ref "T5") (pin "8") (pinfunction "D_8") (pintype "passive"))
    )
    (net (code "56") (name "VBURN4") (class "Default")
      (node (ref "JP7") (pin "3") (pinfunction "3_3") (pintype "passive"))
      (node (ref "T9") (pin "5") (pinfunction "D_5") (pintype "passive"))
      (node (ref "T9") (pin "6") (pinfunction "D_6") (pintype "passive"))
      (node (ref "T9") (pin "7") (pinfunction "D_7") (pintype "passive"))
      (node (ref "T9") (pin "8") (pinfunction "D_8") (pintype "passive"))
    )
    (net (code "57") (name "VBURN_IN") (class "Default")
      (node (ref "R10") (pin "1") (pinfunction "1_1") (pintype "passive"))
      (node (ref "R11") (pin "1") (pinfunction "1_1") (pintype "passive"))
      (node (ref "R12") (pin "2") (pinfunction "2_2") (pintype "passive"))
      (node (ref "R17") (pin "2") (pinfunction "2_2") (pintype "passive"))
      (node (ref "R23") (pin "2") (pinfunction "2_2") (pintype "passive"))
      (node (ref "R6") (pin "2") (pinfunction "2_2") (pintype "passive"))
      (node (ref "T1") (pin "1") (pinfunction "S_1") (pintype "passive"))
      (node (ref "T1") (pin "2") (pinfunction "S_2") (pintype "passive"))
      (node (ref "T1") (pin "3") (pinfunction "S_3") (pintype "passive"))
      (node (ref "T3") (pin "1") (pinfunction "S_1") (pintype "passive"))
      (node (ref "T3") (pin "2") (pinfunction "S_2") (pintype "passive"))
      (node (ref "T3") (pin "3") (pinfunction "S_3") (pintype "passive"))
      (node (ref "T5") (pin "1") (pinfunction "S_1") (pintype "passive"))
      (node (ref "T5") (pin "2") (pinfunction "S_2") (pintype "passive"))
      (node (ref "T5") (pin "3") (pinfunction "S_3") (pintype "passive"))
      (node (ref "T9") (pin "1") (pinfunction "S_1") (pintype "passive"))
      (node (ref "T9") (pin "2") (pinfunction "S_2") (pintype "passive"))
      (node (ref "T9") (pin "3") (pinfunction "S_3") (pintype "passive"))
    )
    (net (code "58") (name "VREG_IN") (class "Default")
      (node (ref "C10") (pin "1") (pinfunction "1_1") (pintype "passive"))
      (node (ref "R7") (pin "1") (pinfunction "1_1") (pintype "passive"))
      (node (ref "U6") (pin "5") (pinfunction "RS-_5") (pintype "bidirectional"))
      (node (ref "U7") (pin "2") (pinfunction "VIN_2") (pintype "bidirectional"))
    )
    (net (code "59") (name "VSOLAR") (class "Default")
      (node (ref "JP1") (pin "2") (pinfunction "2_2") (pintype "passive"))
      (node (ref "JP2") (pin "2") (pinfunction "2_2") (pintype "passive"))
      (node (ref "JP3") (pin "2") (pinfunction "2_2") (pintype "passive"))
      (node (ref "JP4") (pin "2") (pinfunction "2_2") (pintype "passive"))
      (node (ref "JP5") (pin "2") (pinfunction "2_2") (pintype "passive"))
      (node (ref "JP6") (pin "2") (pinfunction "2_2") (pintype "passive"))
      (node (ref "R16") (pin "2") (pinfunction "2_2") (pintype "passive"))
      (node (ref "U8") (pin "4") (pinfunction "RS+_4") (pintype "bidirectional"))
    )
    (net (code "60") (name "unconnected-(JP4-Pad3)") (class "Default")
      (node (ref "JP4") (pin "3") (pinfunction "3_3") (pintype "passive"))
    )
    (net (code "61") (name "unconnected-(JP5-Pad3)") (class "Default")
      (node (ref "JP5") (pin "3") (pinfunction "3_3") (pintype "passive"))
    )
    (net (code "62") (name "unconnected-(JP6-Pad3)") (class "Default")
      (node (ref "JP6") (pin "3") (pinfunction "3_3") (pintype "passive"))
    )
    (net (code "63") (name "unconnected-(JP7-Pad2)") (class "Default")
      (node (ref "JP7") (pin "2") (pinfunction "2_2") (pintype "passive"))
    )
    (net (code "64") (name "unconnected-(JP8-Pad4)") (class "Default")
      (node (ref "JP8") (pin "4") (pinfunction "4_4") (pintype "bidirectional"))
    )
    (net (code "65") (name "unconnected-(S1-Pad1)") (class "Default")
      (node (ref "S1") (pin "1") (pinfunction "1_1") (pintype "bidirectional"))
    )
    (net (code "66") (name "unconnected-(S1-Pad4)") (class "Default")
      (node (ref "S1") (pin "4") (pinfunction "4_4") (pintype "bidirectional"))
    )
    (net (code "67") (name "unconnected-(U1-PadGPIO_0)") (class "Default")
      (node (ref "U1") (pin "GPIO_0") (pinfunction "GPIO_0_GPIO_0") (pintype "bidirectional"))
    )
    (net (code "68") (name "unconnected-(U1-PadGPIO_1)") (class "Default")
      (node (ref "U1") (pin "GPIO_1") (pinfunction "GPIO_1_GPIO_1") (pintype "bidirectional"))
    )
    (net (code "69") (name "unconnected-(U1-PadGPIO_2)") (class "Default")
      (node (ref "U1") (pin "GPIO_2") (pinfunction "GPIO_2_GPIO_2") (pintype "bidirectional"))
    )
    (net (code "70") (name "unconnected-(U1-PadRXON)") (class "Default")
      (node (ref "U1") (pin "RXON") (pinfunction "RXON_RXON") (pintype "bidirectional"))
    )
    (net (code "71") (name "unconnected-(U1-PadTXON)") (class "Default")
      (node (ref "U1") (pin "TXON") (pinfunction "TXON_TXON") (pintype "bidirectional"))
    )
    (net (code "72") (name "unconnected-(U2-*3-Pad6)") (class "Default")
      (node (ref "U2") (pin "6") (pinfunction "*3_6") (pintype "bidirectional"))
    )
    (net (code "73") (name "unconnected-(U2-*5-Pad8)") (class "Default")
      (node (ref "U2") (pin "8") (pinfunction "*5_8") (pintype "bidirectional"))
    )
    (net (code "74") (name "unconnected-(U2-*6-Pad9)") (class "Default")
      (node (ref "U2") (pin "9") (pinfunction "*6_9") (pintype "bidirectional"))
    )
    (net (code "75") (name "unconnected-(U2-*9-Pad12)") (class "Default")
      (node (ref "U2") (pin "12") (pinfunction "*9_12") (pintype "bidirectional"))
    )
    (net (code "76") (name "unconnected-(U2-*10-Pad13)") (class "Default")
      (node (ref "U2") (pin "13") (pinfunction "*10_13") (pintype "bidirectional"))
    )
    (net (code "77") (name "unconnected-(U2-*11-Pad14)") (class "Default")
      (node (ref "U2") (pin "14") (pinfunction "*11_14") (pintype "bidirectional"))
    )
    (net (code "78") (name "unconnected-(U2-2-Pad5)") (class "Default")
      (node (ref "U2") (pin "5") (pinfunction "2_5") (pintype "bidirectional"))
    )
    (net (code "79") (name "unconnected-(U2-4-Pad7)") (class "Default")
      (node (ref "U2") (pin "7") (pinfunction "4_7") (pintype "bidirectional"))
    )
    (net (code "80") (name "unconnected-(U2-7-Pad10)") (class "Default")
      (node (ref "U2") (pin "10") (pinfunction "7_10") (pintype "bidirectional"))
    )
    (net (code "81") (name "unconnected-(U2-8-Pad11)") (class "Default")
      (node (ref "U2") (pin "11") (pinfunction "8_11") (pintype "bidirectional"))
    )
    (net (code "82") (name "unconnected-(U2-13-Pad16)") (class "Default")
      (node (ref "U2") (pin "16") (pinfunction "13_16") (pintype "bidirectional"))
    )
    (net (code "83") (name "unconnected-(U2-A0-Pad17)") (class "Default")
      (node (ref "U2") (pin "17") (pinfunction "A0_17") (pintype "bidirectional"))
    )
    (net (code "84") (name "unconnected-(U2-A1-Pad18)") (class "Default")
      (node (ref "U2") (pin "18") (pinfunction "A1_18") (pintype "bidirectional"))
    )
    (net (code "85") (name "unconnected-(U2-A2-Pad19)") (class "Default")
      (node (ref "U2") (pin "19") (pinfunction "A2_19") (pintype "bidirectional"))
    )
    (net (code "86") (name "unconnected-(U2-A3-Pad20)") (class "Default")
      (node (ref "U2") (pin "20") (pinfunction "A3_20") (pintype "bidirectional"))
    )
    (net (code "87") (name "unconnected-(U2-PadA4)") (class "Default")
      (node (ref "U2") (pin "A4") (pinfunction "A4_A4") (pintype "bidirectional"))
    )
    (net (code "88") (name "unconnected-(U2-PadA5)") (class "Default")
      (node (ref "U2") (pin "A5") (pinfunction "A5_A5") (pintype "bidirectional"))
    )
    (net (code "89") (name "unconnected-(U2-PadA6)") (class "Default")
      (node (ref "U2") (pin "A6") (pinfunction "A6_A6") (pintype "bidirectional"))
    )
    (net (code "90") (name "unconnected-(U2-PadA7)") (class "Default")
      (node (ref "U2") (pin "A7") (pinfunction "A7_A7") (pintype "bidirectional"))
    )
    (net (code "91") (name "unconnected-(U2-RST-Pad3)") (class "Default")
      (node (ref "U2") (pin "3") (pinfunction "RST_3") (pintype "bidirectional"))
    )
    (net (code "92") (name "unconnected-(U3-DRDY-Pad15)") (class "Default")
      (node (ref "U3") (pin "15") (pinfunction "DRDY_15") (pintype "bidirectional"))
    )
    (net (code "93") (name "unconnected-(U3-NC-Pad3)") (class "Default")
      (node (ref "U3") (pin "3") (pinfunction "NC_3") (pintype "bidirectional"))
    )
    (net (code "94") (name "unconnected-(U3-NC-Pad5)") (class "Default")
      (node (ref "U3") (pin "5") (pinfunction "NC_5") (pintype "bidirectional"))
    )
    (net (code "95") (name "unconnected-(U3-NC-Pad6)") (class "Default")
      (node (ref "U3") (pin "6") (pinfunction "NC_6") (pintype "bidirectional"))
    )
    (net (code "96") (name "unconnected-(U3-NC-Pad7)") (class "Default")
      (node (ref "U3") (pin "7") (pinfunction "NC_7") (pintype "bidirectional"))
    )
    (net (code "97") (name "unconnected-(U3-NC-Pad14)") (class "Default")
      (node (ref "U3") (pin "14") (pinfunction "NC_14") (pintype "bidirectional"))
    )
    (net (code "98") (name "unconnected-(U4-Pad20{slash}A6)") (class "Default")
      (node (ref "U4") (pin "20/A6") (pinfunction "20/A6_20/A6") (pintype "bidirectional"))
    )
    (net (code "99") (name "unconnected-(U4-Pad21{slash}A7)") (class "Default")
      (node (ref "U4") (pin "21/A7") (pinfunction "21/A7_21/A7") (pintype "bidirectional"))
    )
    (net (code "100") (name "unconnected-(U4-Pad22{slash}A8)") (class "Default")
      (node (ref "U4") (pin "22/A8") (pinfunction "22/A8_22/A8") (pintype "bidirectional"))
    )
    (net (code "101") (name "unconnected-(U4-PadA10)") (class "Default")
      (node (ref "U4") (pin "A10") (pinfunction "A10_A10") (pintype "bidirectional"))
    )
    (net (code "102") (name "unconnected-(U4-PadA11)") (class "Default")
      (node (ref "U4") (pin "A11") (pinfunction "A11_A11") (pintype "bidirectional"))
    )
    (net (code "103") (name "unconnected-(U4-PadPGM)") (class "Default")
      (node (ref "U4") (pin "PGM") (pinfunction "PGM_PGM") (pintype "bidirectional"))
    )
    (net (code "104") (name "unconnected-(U4-PadRESET)") (class "Default")
      (node (ref "U4") (pin "RESET") (pinfunction "RESET_RESET") (pintype "bidirectional"))
    )
    (net (code "105") (name "unconnected-(U5-INT-Pad12)") (class "Default")
      (node (ref "U5") (pin "12") (pinfunction "INT_12") (pintype "bidirectional"))
    )
    (net (code "106") (name "unconnected-(U7-STATUS-Pad10)") (class "Default")
      (node (ref "U7") (pin "10") (pinfunction "STATUS_10") (pintype "bidirectional"))
    )
  )
)
